# 05_POWER.net
KiCad netlist of a schematic drawn in Altium Designer
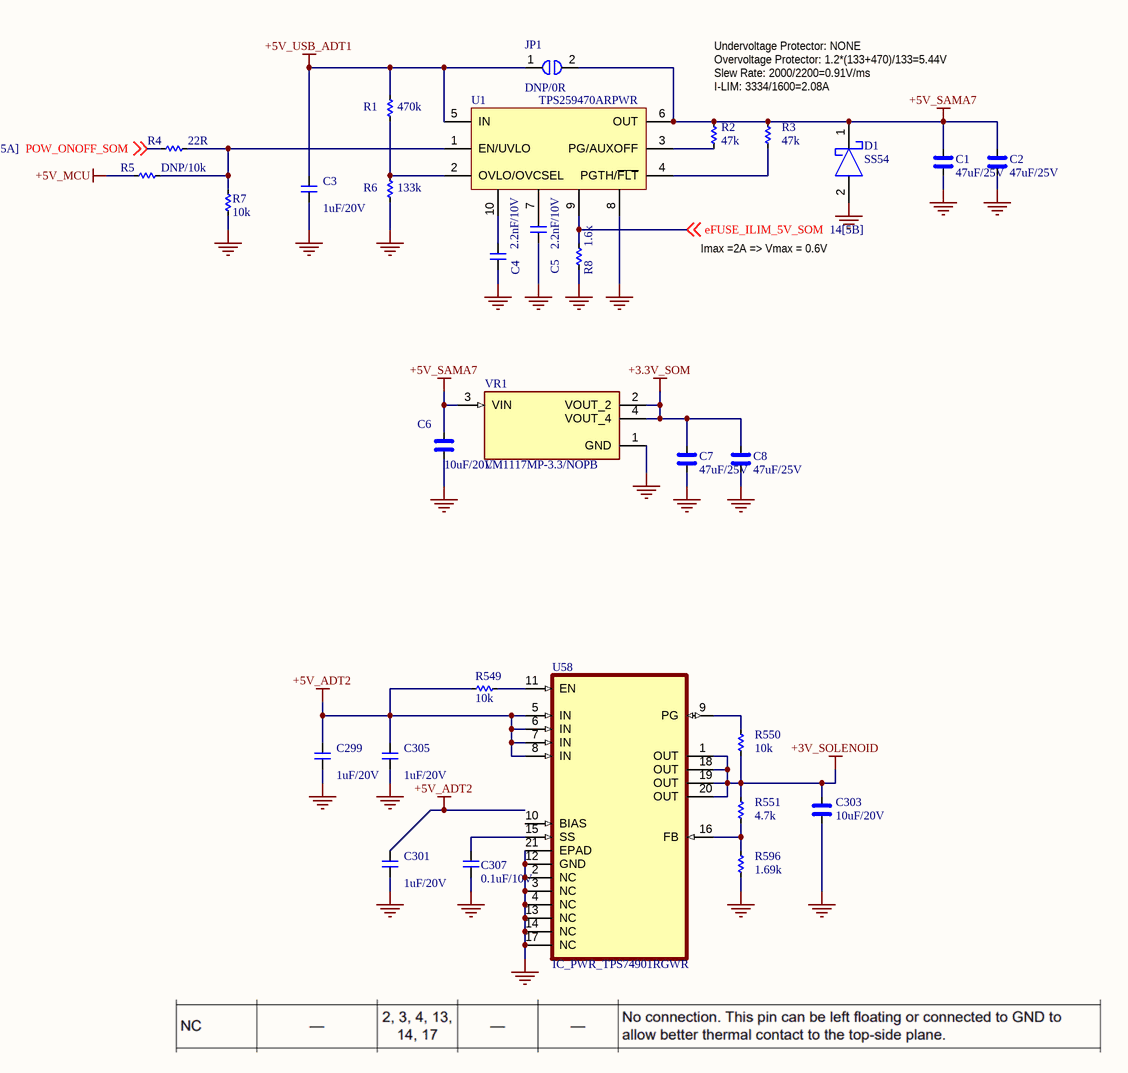
[diagram p0: 05_POWER.SchDoc]

(export (version "E")
  (design (tool "Eeschema 10.0.6"))
  (components
    (comp (ref "C1")
      (value "47uF/25V")
      (footprint "CAP_C_3225X80")
      (description "CAP CHIP High Value")
      (libsource (lib "LABLIB") (part "_CAP_C_High_2"))
    )
    (comp (ref "C2")
      (value "47uF/25V")
      (footprint "CAP_C_3225X80")
      (description "CAP CHIP High Value")
      (libsource (lib "LABLIB") (part "_CAP_C_High_2"))
    )
    (comp (ref "C3")
      (value "1uF/20V")
      (footprint "CAP_C_1005X60")
      (description "CAP CHIP")
      (libsource (lib "LABLIB") (part "_CAP_C_2"))
    )
    (comp (ref "C4")
      (value "2.2nF/10V")
      (footprint "CAP_C_1005X60")
      (description "CAP CHIP")
      (libsource (lib "LABLIB") (part "_CAP_C_2"))
    )
    (comp (ref "C5")
      (value "2.2nF/10V")
      (footprint "CAP_C_1005X60")
      (description "CAP CHIP")
      (libsource (lib "LABLIB") (part "_CAP_C_2"))
    )
    (comp (ref "C6")
      (value "10uF/20V")
      (footprint "CAP_C_2012X110")
      (description "CAP CHIP High Value")
      (libsource (lib "LABLIB") (part "_CAP_C_High_2"))
    )
    (comp (ref "C7")
      (value "47uF/25V")
      (footprint "CAP_C_3225X80")
      (description "CAP CHIP High Value")
      (libsource (lib "LABLIB") (part "_CAP_C_High_2"))
    )
    (comp (ref "C8")
      (value "47uF/25V")
      (footprint "CAP_C_3225X80")
      (description "CAP CHIP High Value")
      (libsource (lib "LABLIB") (part "_CAP_C_High_2"))
    )
    (comp (ref "C299")
      (value "1uF/20V")
      (footprint "CAP_C_1005X60")
      (description "CAP CHIP")
      (libsource (lib "LABLIB") (part "_CAP_C_2"))
    )
    (comp (ref "C301")
      (value "1uF/20V")
      (footprint "CAP_C_1005X60")
      (description "CAP CHIP")
      (libsource (lib "LABLIB") (part "_CAP_C_2"))
    )
    (comp (ref "C303")
      (value "10uF/20V")
      (footprint "CAP_C_2012X110")
      (description "CAP CHIP High Value")
      (libsource (lib "LABLIB") (part "_CAP_C_High_2"))
    )
    (comp (ref "C305")
      (value "1uF/20V")
      (footprint "CAP_C_1005X60")
      (description "CAP CHIP")
      (libsource (lib "LABLIB") (part "_CAP_C_2"))
    )
    (comp (ref "C307")
      (value "0.1uF/10V")
      (footprint "CAP_C_1005X60")
      (description "CAP CHIP")
      (libsource (lib "LABLIB") (part "_CAP_C_2"))
    )
    (comp (ref "D1")
      (value "SS54")
      (footprint "DO-214AC_SMA")
      (description "DIODE SCHOTTKY 60V 3A DO214AA")
      (libsource (lib "EXP_HW_V3") (part "SS54"))
    )
    (comp (ref "JP1")
      (value "DNP/0R")
      (footprint "RES_C_1608X60")
      (libsource (lib "LABLIB") (part "JUMPER_1_1"))
    )
    (comp (ref "R1")
      (value "470k")
      (footprint "RES_C_1005X40")
      (description "RES")
      (libsource (lib "LABLIB") (part "_RES_B_2"))
    )
    (comp (ref "R2")
      (value "47k")
      (footprint "RES_C_1005X40")
      (description "RES")
      (libsource (lib "LABLIB") (part "_RES_B_2"))
    )
    (comp (ref "R3")
      (value "47k")
      (footprint "RES_C_1005X40")
      (description "RES")
      (libsource (lib "LABLIB") (part "_RES_B_2"))
    )
    (comp (ref "R4")
      (value "22R")
      (footprint "RES_C_1005X40")
      (description "RES")
      (libsource (lib "LABLIB") (part "_RES_B_2"))
    )
    (comp (ref "R5")
      (value "DNP/10k")
      (footprint "RES_C_1005X40")
      (description "RES")
      (libsource (lib "LABLIB") (part "_RES_B_2"))
    )
    (comp (ref "R6")
      (value "133k")
      (footprint "RES_C_1005X40")
      (description "RES")
      (libsource (lib "LABLIB") (part "_RES_B_2"))
    )
    (comp (ref "R7")
      (value "10k")
      (footprint "RES_C_1005X40")
      (description "RES")
      (libsource (lib "LABLIB") (part "_RES_B_2"))
    )
    (comp (ref "R8")
      (value "1.6k")
      (footprint "RES_C_1005X40")
      (description "RES")
      (libsource (lib "LABLIB") (part "_RES_B_2"))
    )
    (comp (ref "R549")
      (value "10k")
      (footprint "RES_C_1005X40")
      (description "RES")
      (libsource (lib "LABLIB") (part "_RES_B_2"))
    )
    (comp (ref "R550")
      (value "10k")
      (footprint "RES_C_1005X40")
      (description "RES")
      (libsource (lib "LABLIB") (part "_RES_B_2"))
    )
    (comp (ref "R551")
      (value "4.7k")
      (footprint "RES_C_1005X40")
      (description "RES")
      (libsource (lib "LABLIB") (part "_RES_B_2"))
    )
    (comp (ref "R596")
      (value "1.69k")
      (footprint "RES_C_1005X40")
      (description "RES")
      (libsource (lib "LABLIB") (part "_RES_B_2"))
    )
    (comp (ref "U1")
      (value "TPS259470ARPWR")
      (footprint "VQFN-HR-10")
      (libsource (lib "EXP_HW_V3") (part "TPS259470ARPWR"))
    )
    (comp (ref "U58")
      (value "IC_PWR_TPS74901RGWR")
      (footprint "QFN65P500X500X100-21N:QFN65P500X500X100-21N")
      (fields (field (name "MF") "Texas Instruments") (field (name "MP") "TPS74901RGWR"))
      (libsource (lib "LABLIB") (part "IC_PWR_TPS74901RGWR"))
    )
    (comp (ref "VR1")
      (value "LM1117MP-3.3/NOPB")
      (footprint "VREG_LM1117MP-3.3/NOPB")
      (description "800-mA 15-V linear voltage regulator")
      (fields (field (name "MF") "Texas Instruments"))
      (libsource (lib "new_component") (part "LM1117MP-3.3/NOPB"))
    )
  )
  (nets
    (net (code "1") (name "+3.3V_SOM") (class "Default")
      (node (ref "C7") (pin "2") (pinfunction "2_2") (pintype "passive"))
      (node (ref "C8") (pin "2") (pinfunction "2_2") (pintype "passive"))
      (node (ref "VR1") (pin "2") (pinfunction "VOUT_2_2") (pintype "power_in"))
      (node (ref "VR1") (pin "4") (pinfunction "VOUT_4_4") (pintype "power_in"))
    )
    (net (code "2") (name "+3V_SOLENOID") (class "Default")
      (node (ref "C303") (pin "1") (pinfunction "1_1") (pintype "passive"))
      (node (ref "R550") (pin "1") (pinfunction "1_1") (pintype "passive"))
      (node (ref "R551") (pin "2") (pinfunction "2_2") (pintype "passive"))
      (node (ref "U58") (pin "1") (pinfunction "OUT_1") (pintype "passive"))
      (node (ref "U58") (pin "18") (pinfunction "OUT_18") (pintype "passive"))
      (node (ref "U58") (pin "19") (pinfunction "OUT_19") (pintype "passive"))
      (node (ref "U58") (pin "20") (pinfunction "OUT_20") (pintype "passive"))
    )
    (net (code "3") (name "+5V_ADT2") (class "Default")
      (node (ref "C299") (pin "2") (pinfunction "2_2") (pintype "passive"))
      (node (ref "C301") (pin "2") (pinfunction "2_2") (pintype "passive"))
      (node (ref "C305") (pin "2") (pinfunction "2_2") (pintype "passive"))
      (node (ref "R549") (pin "2") (pinfunction "2_2") (pintype "passive"))
      (node (ref "U58") (pin "5") (pinfunction "IN_5") (pintype "input"))
      (node (ref "U58") (pin "6") (pinfunction "IN_6") (pintype "input"))
      (node (ref "U58") (pin "7") (pinfunction "IN_7") (pintype "input"))
      (node (ref "U58") (pin "8") (pinfunction "IN_8") (pintype "input"))
    )
    (net (code "4") (name "+5V_MCU") (class "Default")
      (node (ref "R5") (pin "2") (pinfunction "2_2") (pintype "passive"))
    )
    (net (code "5") (name "+5V_SAMA7") (class "Default")
      (node (ref "C1") (pin "2") (pinfunction "2_2") (pintype "passive"))
      (node (ref "C2") (pin "2") (pinfunction "2_2") (pintype "passive"))
      (node (ref "C6") (pin "1") (pinfunction "1_1") (pintype "passive"))
      (node (ref "D1") (pin "1") (pinfunction "1_1") (pintype "passive"))
      (node (ref "JP1") (pin "2") (pinfunction "2_2") (pintype "passive"))
      (node (ref "R2") (pin "2") (pinfunction "2_2") (pintype "passive"))
      (node (ref "R3") (pin "2") (pinfunction "2_2") (pintype "passive"))
      (node (ref "U1") (pin "6") (pinfunction "OUT_6") (pintype "passive"))
      (node (ref "VR1") (pin "3") (pinfunction "VIN_3") (pintype "input"))
    )
    (net (code "6") (name "+5V_USB_ADT1") (class "Default")
      (node (ref "C3") (pin "2") (pinfunction "2_2") (pintype "passive"))
      (node (ref "JP1") (pin "1") (pinfunction "1_1") (pintype "passive"))
      (node (ref "R1") (pin "2") (pinfunction "2_2") (pintype "passive"))
      (node (ref "U1") (pin "5") (pinfunction "IN_5") (pintype "passive"))
    )
    (net (code "7") (name "GND") (class "Default")
      (node (ref "C1") (pin "1") (pinfunction "1_1") (pintype "passive"))
      (node (ref "C2") (pin "1") (pinfunction "1_1") (pintype "passive"))
      (node (ref "C299") (pin "1") (pinfunction "1_1") (pintype "passive"))
      (node (ref "C3") (pin "1") (pinfunction "1_1") (pintype "passive"))
      (node (ref "C301") (pin "1") (pinfunction "1_1") (pintype "passive"))
      (node (ref "C303") (pin "2") (pinfunction "2_2") (pintype "passive"))
      (node (ref "C305") (pin "1") (pinfunction "1_1") (pintype "passive"))
      (node (ref "C307") (pin "1") (pinfunction "1_1") (pintype "passive"))
      (node (ref "C4") (pin "1") (pinfunction "1_1") (pintype "passive"))
      (node (ref "C5") (pin "1") (pinfunction "1_1") (pintype "passive"))
      (node (ref "C6") (pin "2") (pinfunction "2_2") (pintype "passive"))
      (node (ref "C7") (pin "1") (pinfunction "1_1") (pintype "passive"))
      (node (ref "C8") (pin "1") (pinfunction "1_1") (pintype "passive"))
      (node (ref "D1") (pin "2") (pinfunction "2_2") (pintype "passive"))
      (node (ref "R596") (pin "1") (pinfunction "1_1") (pintype "passive"))
      (node (ref "R6") (pin "1") (pinfunction "1_1") (pintype "passive"))
      (node (ref "R7") (pin "2") (pinfunction "2_2") (pintype "passive"))
      (node (ref "R8") (pin "1") (pinfunction "1_1") (pintype "passive"))
      (node (ref "U1") (pin "8") (pinfunction "8_8") (pintype "passive"))
      (node (ref "U58") (pin "12") (pinfunction "GND_12") (pintype "power_in"))
      (node (ref "U58") (pin "13") (pinfunction "NC_13") (pintype "passive"))
      (node (ref "U58") (pin "14") (pinfunction "NC_14") (pintype "passive"))
      (node (ref "U58") (pin "17") (pinfunction "NC_17") (pintype "passive"))
      (node (ref "U58") (pin "2") (pinfunction "NC_2") (pintype "passive"))
      (node (ref "U58") (pin "21") (pinfunction "EPAD_21") (pintype "power_in"))
      (node (ref "U58") (pin "3") (pinfunction "NC_3") (pintype "passive"))
      (node (ref "U58") (pin "4") (pinfunction "NC_4") (pintype "passive"))
      (node (ref "VR1") (pin "1") (pinfunction "GND_1") (pintype "power_in"))
    )
    (net (code "8") (name "Net-(C4-Pad2)") (class "Default")
      (node (ref "C4") (pin "2") (pinfunction "2_2") (pintype "passive"))
      (node (ref "U1") (pin "10") (pinfunction "10_10") (pintype "passive"))
    )
    (net (code "9") (name "Net-(C5-Pad2)") (class "Default")
      (node (ref "C5") (pin "2") (pinfunction "2_2") (pintype "passive"))
      (node (ref "U1") (pin "7") (pinfunction "7_7") (pintype "passive"))
    )
    (net (code "10") (name "Net-(U1-EN{slash}UVLO)") (class "Default")
      (node (ref "R4") (pin "1") (pinfunction "1_1") (pintype "passive"))
      (node (ref "R5") (pin "1") (pinfunction "1_1") (pintype "passive"))
      (node (ref "R7") (pin "1") (pinfunction "1_1") (pintype "passive"))
      (node (ref "U1") (pin "1") (pinfunction "EN/UVLO_1") (pintype "passive"))
    )
    (net (code "11") (name "Net-(U1-OVLO{slash}OVCSEL)") (class "Default")
      (node (ref "R1") (pin "1") (pinfunction "1_1") (pintype "passive"))
      (node (ref "R6") (pin "2") (pinfunction "2_2") (pintype "passive"))
      (node (ref "U1") (pin "2") (pinfunction "OVLO/OVCSEL_2") (pintype "passive"))
    )
    (net (code "12") (name "Net-(U1-PGTH{slash}~{FLT})") (class "Default")
      (node (ref "R3") (pin "1") (pinfunction "1_1") (pintype "passive"))
      (node (ref "U1") (pin "4") (pinfunction "PGTH/~{FLT}_4") (pintype "passive"))
    )
    (net (code "13") (name "Net-(U1-PG{slash}AUXOFF)") (class "Default")
      (node (ref "R2") (pin "1") (pinfunction "1_1") (pintype "passive"))
      (node (ref "U1") (pin "3") (pinfunction "PG/AUXOFF_3") (pintype "passive"))
    )
    (net (code "14") (name "Net-(U58-EN)") (class "Default")
      (node (ref "R549") (pin "1") (pinfunction "1_1") (pintype "passive"))
      (node (ref "U58") (pin "11") (pinfunction "EN_11") (pintype "input"))
    )
    (net (code "15") (name "Net-(U58-FB)") (class "Default")
      (node (ref "R551") (pin "1") (pinfunction "1_1") (pintype "passive"))
      (node (ref "R596") (pin "2") (pinfunction "2_2") (pintype "passive"))
      (node (ref "U58") (pin "16") (pinfunction "FB_16") (pintype "input"))
    )
    (net (code "16") (name "Net-(U58-PG)") (class "Default")
      (node (ref "R550") (pin "2") (pinfunction "2_2") (pintype "passive"))
      (node (ref "U58") (pin "9") (pinfunction "PG_9") (pintype "bidirectional"))
    )
    (net (code "17") (name "Net-(U58-SS)") (class "Default")
      (node (ref "C307") (pin "2") (pinfunction "2_2") (pintype "passive"))
      (node (ref "U58") (pin "15") (pinfunction "SS_15") (pintype "input"))
    )
    (net (code "18") (name "POW_ONOFF_SOM") (class "Default")
      (node (ref "R4") (pin "2") (pinfunction "2_2") (pintype "passive"))
    )
    (net (code "19") (name "eFUSE_ILIM_5V_SOM") (class "Default")
      (node (ref "R8") (pin "2") (pinfunction "2_2") (pintype "passive"))
      (node (ref "U1") (pin "9") (pinfunction "9_9") (pintype "passive"))
    )
    (net (code "20") (name "unconnected-(U58-BIAS-Pad10)") (class "Default")
      (node (ref "U58") (pin "10") (pinfunction "BIAS_10") (pintype "input"))
    )
  )
)
